# Main.net
KiCad netlist of a schematic drawn in Altium Designer
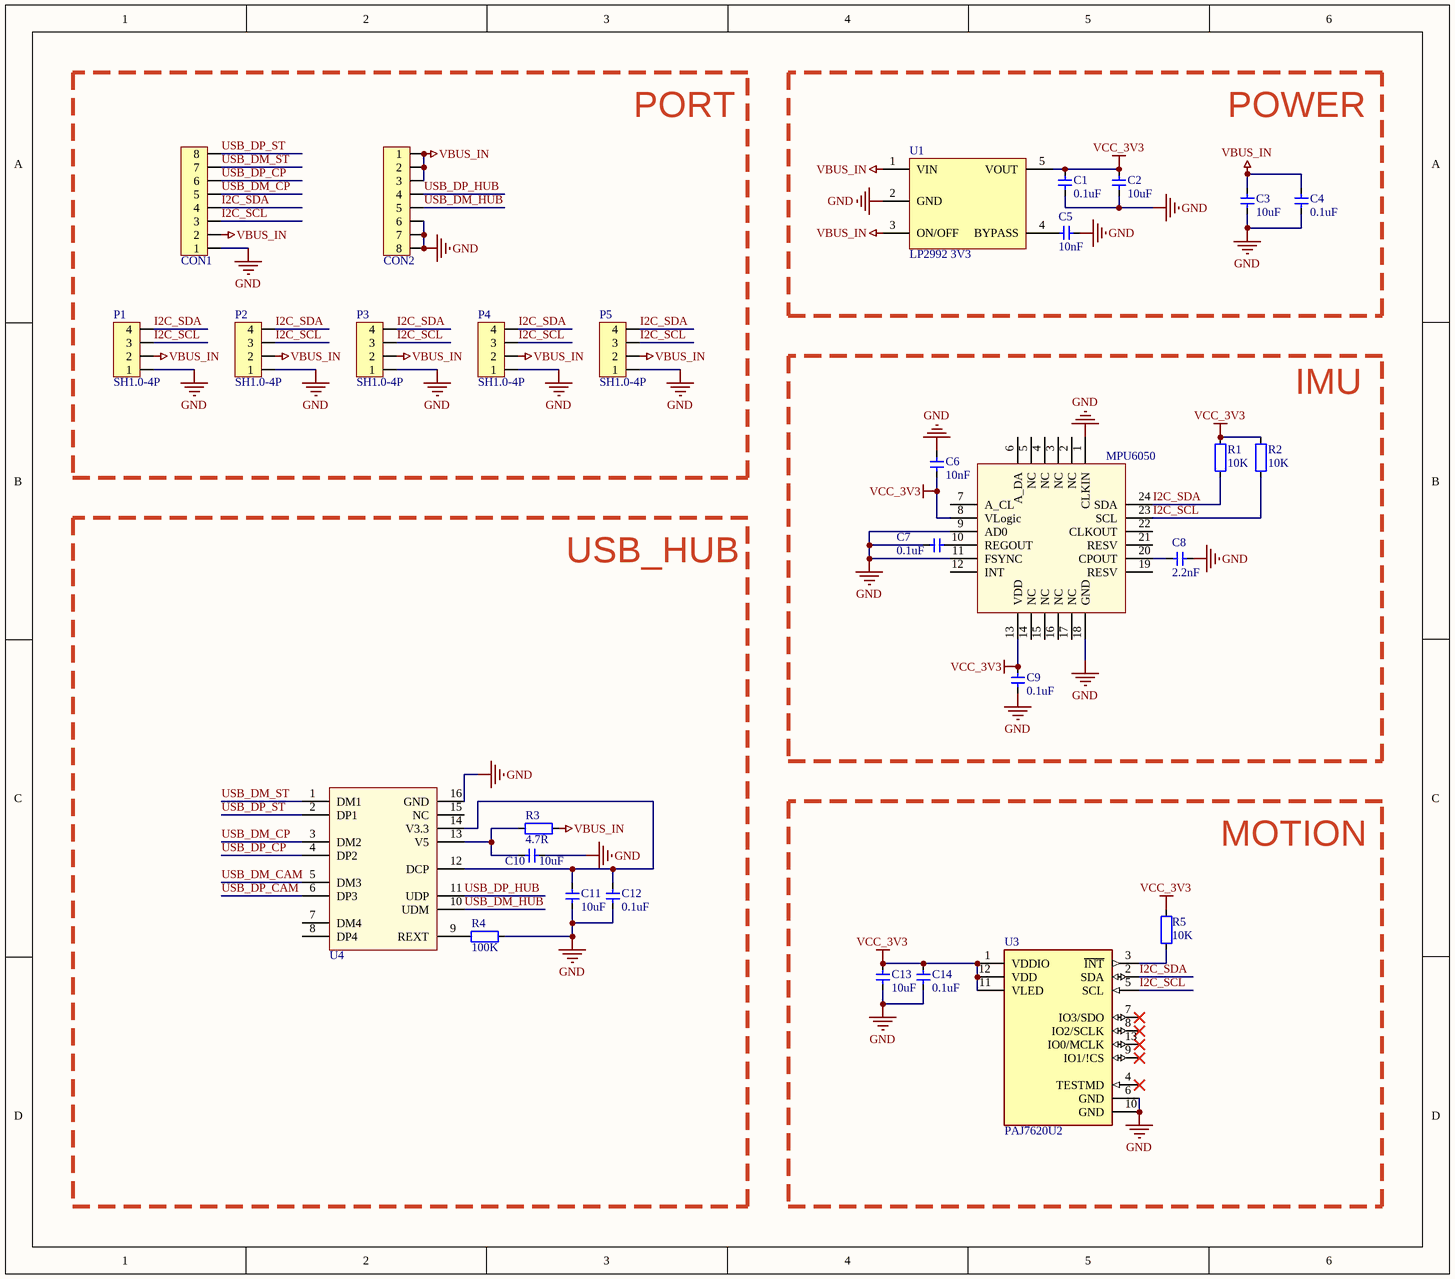
[diagram p0: Main.SchDoc]

(export (version "E")
  (design (tool "Eeschema 10.0.6"))
  (components
    (comp (ref "C1")
      (value "0.1uF")
      (footprint "CAP_0402")
      (description "Capacitor")
      (libsource (lib "MyPcbLib") (part "电容-0402"))
    )
    (comp (ref "C2")
      (value "10uF")
      (footprint "CAP_0402")
      (description "Capacitor")
      (libsource (lib "MyPcbLib") (part "电容-0402"))
    )
    (comp (ref "C3")
      (value "10uF")
      (footprint "CAP_0402")
      (description "Capacitor")
      (libsource (lib "MyPcbLib") (part "电容-0402"))
    )
    (comp (ref "C4")
      (value "0.1uF")
      (footprint "CAP_0402")
      (description "Capacitor")
      (libsource (lib "MyPcbLib") (part "电容-0402"))
    )
    (comp (ref "C5")
      (value "10nF")
      (footprint "CAP_0402")
      (description "Capacitor")
      (libsource (lib "MyPcbLib") (part "电容-0402"))
    )
    (comp (ref "C6")
      (value "10nF")
      (footprint "CAP_0402")
      (description "Capacitor")
      (libsource (lib "MyPcbLib") (part "电容-0402"))
    )
    (comp (ref "C7")
      (value "0.1uF")
      (footprint "CAP_0402")
      (description "Capacitor")
      (libsource (lib "MyPcbLib") (part "电容-0402"))
    )
    (comp (ref "C8")
      (value "2.2nF")
      (footprint "CAP_0402")
      (description "Capacitor")
      (libsource (lib "MyPcbLib") (part "电容-0402"))
    )
    (comp (ref "C9")
      (value "0.1uF")
      (footprint "CAP_0402")
      (description "Capacitor")
      (libsource (lib "MyPcbLib") (part "电容-0402"))
    )
    (comp (ref "C10")
      (value "10uF")
      (footprint "CAP_0402")
      (description "Capacitor")
      (libsource (lib "MyPcbLib") (part "电容-0402"))
    )
    (comp (ref "C11")
      (value "10uF")
      (footprint "CAP_0402")
      (description "Capacitor")
      (libsource (lib "MyPcbLib") (part "电容-0402"))
    )
    (comp (ref "C12")
      (value "0.1uF")
      (footprint "CAP_0402")
      (description "Capacitor")
      (libsource (lib "MyPcbLib") (part "电容-0402"))
    )
    (comp (ref "C13")
      (value "10uF")
      (footprint "CAP_0402")
      (description "Capacitor")
      (libsource (lib "MyPcbLib") (part "电容-0402"))
    )
    (comp (ref "C14")
      (value "0.1uF")
      (footprint "CAP_0402")
      (description "Capacitor")
      (libsource (lib "MyPcbLib") (part "电容-0402"))
    )
    (comp (ref "CON1")
      (value "FFC_0.5_8")
      (footprint "FFC_0.5_8")
      (description "FFC")
      (libsource (lib "KitSprout") (part "FFC_0.5_8"))
    )
    (comp (ref "CON2")
      (value "FFC_0.5_8")
      (footprint "FFC_0.5_8")
      (description "FFC")
      (libsource (lib "") (part "FFC_0.5_8_1"))
    )
    (comp (ref "P1") (value "SH1.0-4P") (footprint "SH1.0-4P") (libsource (lib "MyPcbLib") (part "SH1.0-4P")))
    (comp (ref "P2") (value "SH1.0-4P") (footprint "SH1.0-4P") (libsource (lib "MyPcbLib") (part "SH1.0-4P")))
    (comp (ref "P3") (value "SH1.0-4P") (footprint "SH1.0-4P") (libsource (lib "MyPcbLib") (part "SH1.0-4P")))
    (comp (ref "P4") (value "SH1.0-4P") (footprint "SH1.0-4P") (libsource (lib "MyPcbLib") (part "SH1.0-4P")))
    (comp (ref "P5") (value "SH1.0-4P") (footprint "SH1.0-4P") (libsource (lib "MyPcbLib") (part "SH1.0-4P")))
    (comp (ref "R1")
      (value "10K")
      (footprint "RES_0402")
      (description "Resistor")
      (libsource (lib "") (part "电阻-0402_1"))
    )
    (comp (ref "R2")
      (value "10K")
      (footprint "RES_0402")
      (description "Resistor")
      (libsource (lib "") (part "电阻-0402_1"))
    )
    (comp (ref "R3")
      (value "4.7R")
      (footprint "RES_0402")
      (description "Resistor")
      (libsource (lib "MyPcbLib") (part "电阻-0402"))
    )
    (comp (ref "R4")
      (value "100K")
      (footprint "RES_0402")
      (description "Resistor")
      (libsource (lib "MyPcbLib") (part "电阻-0402"))
    )
    (comp (ref "R5")
      (value "10K")
      (footprint "RES_0402")
      (description "Resistor")
      (libsource (lib "") (part "电阻-0402_2"))
    )
    (comp (ref "U1")
      (value "LP2992 3V3")
      (footprint "SOT23-5")
      (description "LDO")
      (libsource (lib "MyPcbLib") (part "LP2992"))
    )
    (comp (ref "U2")
      (value "MPU6050")
      (footprint "QFN-24")
      (description "六轴传感器")
      (libsource (lib "mLib") (part "MPU6050"))
    )
    (comp (ref "U3")
      (value "PAJ7620U2")
      (footprint "PAJ7620U2")
      (description "module sensorPAJ7620U2 : 54/TRAY, 5400/BOX, 32400/CARTON")
      (fields (field (name "MF") "Pixart"))
      (libsource (lib "MyPcbLib") (part "PAJ7620U2"))
    )
    (comp (ref "U4")
      (value "HS8836A")
      (footprint "SO-16N")
      (description "USB2.0 HUB")
      (libsource (lib "MyPcbLib") (part "HS8836A"))
    )
  )
  (nets
    (net (code "1") (name "/I2C_SCL") (class "Default")
      (node (ref "CON1") (pin "3") (pinfunction "3_3") (pintype "passive"))
      (node (ref "P1") (pin "3") (pinfunction "3_3") (pintype "passive"))
      (node (ref "P2") (pin "3") (pinfunction "3_3") (pintype "passive"))
      (node (ref "P3") (pin "3") (pinfunction "3_3") (pintype "passive"))
      (node (ref "P4") (pin "3") (pinfunction "3_3") (pintype "passive"))
      (node (ref "P5") (pin "3") (pinfunction "3_3") (pintype "passive"))
      (node (ref "R2") (pin "1") (pinfunction "1_1") (pintype "passive"))
      (node (ref "U2") (pin "23") (pinfunction "SCL_23") (pintype "passive"))
      (node (ref "U3") (pin "5") (pinfunction "SCL_5") (pintype "input"))
    )
    (net (code "2") (name "/I2C_SDA") (class "Default")
      (node (ref "CON1") (pin "4") (pinfunction "4_4") (pintype "passive"))
      (node (ref "P1") (pin "4") (pinfunction "4_4") (pintype "passive"))
      (node (ref "P2") (pin "4") (pinfunction "4_4") (pintype "passive"))
      (node (ref "P3") (pin "4") (pinfunction "4_4") (pintype "passive"))
      (node (ref "P4") (pin "4") (pinfunction "4_4") (pintype "passive"))
      (node (ref "P5") (pin "4") (pinfunction "4_4") (pintype "passive"))
      (node (ref "R1") (pin "1") (pinfunction "1_1") (pintype "passive"))
      (node (ref "U2") (pin "24") (pinfunction "SDA_24") (pintype "passive"))
      (node (ref "U3") (pin "2") (pinfunction "SDA_2") (pintype "bidirectional"))
    )
    (net (code "3") (name "/USB_DM_CAM") (class "Default")
      (node (ref "U4") (pin "5") (pinfunction "DM3_5") (pintype "passive"))
    )
    (net (code "4") (name "/USB_DM_CP") (class "Default")
      (node (ref "CON1") (pin "5") (pinfunction "5_5") (pintype "passive"))
      (node (ref "U4") (pin "3") (pinfunction "DM2_3") (pintype "passive"))
    )
    (net (code "5") (name "/USB_DM_HUB") (class "Default")
      (node (ref "CON2") (pin "5") (pinfunction "5_5") (pintype "passive"))
      (node (ref "U4") (pin "10") (pinfunction "UDM_10") (pintype "passive"))
    )
    (net (code "6") (name "/USB_DM_ST") (class "Default")
      (node (ref "CON1") (pin "7") (pinfunction "7_7") (pintype "passive"))
      (node (ref "U4") (pin "1") (pinfunction "DM1_1") (pintype "passive"))
    )
    (net (code "7") (name "/USB_DP_CAM") (class "Default")
      (node (ref "U4") (pin "6") (pinfunction "DP3_6") (pintype "passive"))
    )
    (net (code "8") (name "/USB_DP_CP") (class "Default")
      (node (ref "CON1") (pin "6") (pinfunction "6_6") (pintype "passive"))
      (node (ref "U4") (pin "4") (pinfunction "DP2_4") (pintype "passive"))
    )
    (net (code "9") (name "/USB_DP_HUB") (class "Default")
      (node (ref "CON2") (pin "4") (pinfunction "4_4") (pintype "passive"))
      (node (ref "U4") (pin "11") (pinfunction "UDP_11") (pintype "passive"))
    )
    (net (code "10") (name "/USB_DP_ST") (class "Default")
      (node (ref "CON1") (pin "8") (pinfunction "8_8") (pintype "passive"))
      (node (ref "U4") (pin "2") (pinfunction "DP1_2") (pintype "passive"))
    )
    (net (code "11") (name "GND") (class "Default")
      (node (ref "C1") (pin "1") (pinfunction "1_1") (pintype "passive"))
      (node (ref "C10") (pin "1") (pinfunction "1_1") (pintype "passive"))
      (node (ref "C11") (pin "2") (pinfunction "2_2") (pintype "passive"))
      (node (ref "C12") (pin "2") (pinfunction "2_2") (pintype "passive"))
      (node (ref "C13") (pin "2") (pinfunction "2_2") (pintype "passive"))
      (node (ref "C14") (pin "2") (pinfunction "2_2") (pintype "passive"))
      (node (ref "C2") (pin "1") (pinfunction "1_1") (pintype "passive"))
      (node (ref "C3") (pin "1") (pinfunction "1_1") (pintype "passive"))
      (node (ref "C4") (pin "1") (pinfunction "1_1") (pintype "passive"))
      (node (ref "C5") (pin "1") (pinfunction "1_1") (pintype "passive"))
      (node (ref "C6") (pin "2") (pinfunction "2_2") (pintype "passive"))
      (node (ref "C7") (pin "2") (pinfunction "2_2") (pintype "passive"))
      (node (ref "C8") (pin "1") (pinfunction "1_1") (pintype "passive"))
      (node (ref "C9") (pin "1") (pinfunction "1_1") (pintype "passive"))
      (node (ref "CON1") (pin "1") (pinfunction "1_1") (pintype "passive"))
      (node (ref "CON2") (pin "6") (pinfunction "6_6") (pintype "passive"))
      (node (ref "CON2") (pin "7") (pinfunction "7_7") (pintype "passive"))
      (node (ref "CON2") (pin "8") (pinfunction "8_8") (pintype "passive"))
      (node (ref "P1") (pin "1") (pinfunction "1_1") (pintype "passive"))
      (node (ref "P2") (pin "1") (pinfunction "1_1") (pintype "passive"))
      (node (ref "P3") (pin "1") (pinfunction "1_1") (pintype "passive"))
      (node (ref "P4") (pin "1") (pinfunction "1_1") (pintype "passive"))
      (node (ref "P5") (pin "1") (pinfunction "1_1") (pintype "passive"))
      (node (ref "R4") (pin "1") (pinfunction "1_1") (pintype "passive"))
      (node (ref "U1") (pin "2") (pinfunction "GND_2") (pintype "passive"))
      (node (ref "U2") (pin "1") (pinfunction "CLKIN_1") (pintype "passive"))
      (node (ref "U2") (pin "11") (pinfunction "FSYNC_11") (pintype "passive"))
      (node (ref "U2") (pin "18") (pinfunction "GND_18") (pintype "passive"))
      (node (ref "U2") (pin "9") (pinfunction "AD0_9") (pintype "passive"))
      (node (ref "U3") (pin "10") (pinfunction "GND_10") (pintype "passive"))
      (node (ref "U3") (pin "6") (pinfunction "GND_6") (pintype "passive"))
      (node (ref "U4") (pin "16") (pinfunction "GND_16") (pintype "passive"))
    )
    (net (code "12") (name "Net-(U1-BYPASS)") (class "Default")
      (node (ref "C5") (pin "2") (pinfunction "2_2") (pintype "passive"))
      (node (ref "U1") (pin "4") (pinfunction "BYPASS_4") (pintype "passive"))
    )
    (net (code "13") (name "Net-(U2-CPOUT)") (class "Default")
      (node (ref "C8") (pin "2") (pinfunction "2_2") (pintype "passive"))
      (node (ref "U2") (pin "20") (pinfunction "CPOUT_20") (pintype "passive"))
    )
    (net (code "14") (name "Net-(U2-REGOUT)") (class "Default")
      (node (ref "C7") (pin "1") (pinfunction "1_1") (pintype "passive"))
      (node (ref "U2") (pin "10") (pinfunction "REGOUT_10") (pintype "passive"))
    )
    (net (code "15") (name "Net-(U3-~{INT})") (class "Default")
      (node (ref "R5") (pin "2") (pinfunction "2_2") (pintype "passive"))
      (node (ref "U3") (pin "3") (pinfunction "~{INT}_3") (pintype "output"))
    )
    (net (code "16") (name "Net-(U4-DCP)") (class "Default")
      (node (ref "C11") (pin "1") (pinfunction "1_1") (pintype "passive"))
      (node (ref "C12") (pin "1") (pinfunction "1_1") (pintype "passive"))
      (node (ref "U4") (pin "12") (pinfunction "DCP_12") (pintype "passive"))
      (node (ref "U4") (pin "14") (pinfunction "V3.3_14") (pintype "passive"))
    )
    (net (code "17") (name "Net-(U4-REXT)") (class "Default")
      (node (ref "R4") (pin "2") (pinfunction "2_2") (pintype "passive"))
      (node (ref "U4") (pin "9") (pinfunction "REXT_9") (pintype "passive"))
    )
    (net (code "18") (name "Net-(U4-V5)") (class "Default")
      (node (ref "C10") (pin "2") (pinfunction "2_2") (pintype "passive"))
      (node (ref "R3") (pin "2") (pinfunction "2_2") (pintype "passive"))
      (node (ref "U4") (pin "13") (pinfunction "V5_13") (pintype "passive"))
    )
    (net (code "19") (name "VBUS_IN") (class "Default")
      (node (ref "C3") (pin "2") (pinfunction "2_2") (pintype "passive"))
      (node (ref "C4") (pin "2") (pinfunction "2_2") (pintype "passive"))
      (node (ref "CON1") (pin "2") (pinfunction "2_2") (pintype "passive"))
      (node (ref "CON2") (pin "1") (pinfunction "1_1") (pintype "passive"))
      (node (ref "CON2") (pin "2") (pinfunction "2_2") (pintype "passive"))
      (node (ref "CON2") (pin "3") (pinfunction "3_3") (pintype "passive"))
      (node (ref "P1") (pin "2") (pinfunction "2_2") (pintype "passive"))
      (node (ref "P2") (pin "2") (pinfunction "2_2") (pintype "passive"))
      (node (ref "P3") (pin "2") (pinfunction "2_2") (pintype "passive"))
      (node (ref "P4") (pin "2") (pinfunction "2_2") (pintype "passive"))
      (node (ref "P5") (pin "2") (pinfunction "2_2") (pintype "passive"))
      (node (ref "R3") (pin "1") (pinfunction "1_1") (pintype "passive"))
      (node (ref "U1") (pin "1") (pinfunction "VIN_1") (pintype "passive"))
      (node (ref "U1") (pin "3") (pinfunction "ON/OFF_3") (pintype "passive"))
    )
    (net (code "20") (name "VCC_3V3") (class "Default")
      (node (ref "C1") (pin "2") (pinfunction "2_2") (pintype "passive"))
      (node (ref "C13") (pin "1") (pinfunction "1_1") (pintype "passive"))
      (node (ref "C14") (pin "1") (pinfunction "1_1") (pintype "passive"))
      (node (ref "C2") (pin "2") (pinfunction "2_2") (pintype "passive"))
      (node (ref "C6") (pin "1") (pinfunction "1_1") (pintype "passive"))
      (node (ref "C9") (pin "2") (pinfunction "2_2") (pintype "passive"))
      (node (ref "R1") (pin "2") (pinfunction "2_2") (pintype "passive"))
      (node (ref "R2") (pin "2") (pinfunction "2_2") (pintype "passive"))
      (node (ref "R5") (pin "1") (pinfunction "1_1") (pintype "passive"))
      (node (ref "U1") (pin "5") (pinfunction "VOUT_5") (pintype "passive"))
      (node (ref "U2") (pin "13") (pinfunction "VDD_13") (pintype "passive"))
      (node (ref "U2") (pin "8") (pinfunction "VLogic_8") (pintype "passive"))
      (node (ref "U3") (pin "1") (pinfunction "VDDIO_1") (pintype "power_in"))
      (node (ref "U3") (pin "11") (pinfunction "VLED_11") (pintype "power_in"))
      (node (ref "U3") (pin "12") (pinfunction "VDD_12") (pintype "power_in"))
    )
    (net (code "21") (name "unconnected-(U2-A_CL-Pad7)") (class "Default")
      (node (ref "U2") (pin "7") (pinfunction "A_CL_7") (pintype "passive"))
    )
    (net (code "22") (name "unconnected-(U2-A_DA-Pad6)") (class "Default")
      (node (ref "U2") (pin "6") (pinfunction "A_DA_6") (pintype "passive"))
    )
    (net (code "23") (name "unconnected-(U2-CLKOUT-Pad22)") (class "Default")
      (node (ref "U2") (pin "22") (pinfunction "CLKOUT_22") (pintype "passive"))
    )
    (net (code "24") (name "unconnected-(U2-INT-Pad12)") (class "Default")
      (node (ref "U2") (pin "12") (pinfunction "INT_12") (pintype "passive"))
    )
    (net (code "25") (name "unconnected-(U2-NC-Pad2)") (class "Default")
      (node (ref "U2") (pin "2") (pinfunction "NC_2") (pintype "passive"))
    )
    (net (code "26") (name "unconnected-(U2-NC-Pad3)") (class "Default")
      (node (ref "U2") (pin "3") (pinfunction "NC_3") (pintype "passive"))
    )
    (net (code "27") (name "unconnected-(U2-NC-Pad4)") (class "Default")
      (node (ref "U2") (pin "4") (pinfunction "NC_4") (pintype "passive"))
    )
    (net (code "28") (name "unconnected-(U2-NC-Pad5)") (class "Default")
      (node (ref "U2") (pin "5") (pinfunction "NC_5") (pintype "passive"))
    )
    (net (code "29") (name "unconnected-(U2-NC-Pad14)") (class "Default")
      (node (ref "U2") (pin "14") (pinfunction "NC_14") (pintype "passive"))
    )
    (net (code "30") (name "unconnected-(U2-NC-Pad15)") (class "Default")
      (node (ref "U2") (pin "15") (pinfunction "NC_15") (pintype "passive"))
    )
    (net (code "31") (name "unconnected-(U2-NC-Pad16)") (class "Default")
      (node (ref "U2") (pin "16") (pinfunction "NC_16") (pintype "passive"))
    )
    (net (code "32") (name "unconnected-(U2-NC-Pad17)") (class "Default")
      (node (ref "U2") (pin "17") (pinfunction "NC_17") (pintype "passive"))
    )
    (net (code "33") (name "unconnected-(U2-RESV-Pad19)") (class "Default")
      (node (ref "U2") (pin "19") (pinfunction "RESV_19") (pintype "passive"))
    )
    (net (code "34") (name "unconnected-(U2-RESV-Pad21)") (class "Default")
      (node (ref "U2") (pin "21") (pinfunction "RESV_21") (pintype "passive"))
    )
    (net (code "35") (name "unconnected-(U3-IO0{slash}MCLK-Pad13)") (class "Default")
      (node (ref "U3") (pin "13") (pinfunction "IO0/MCLK_13") (pintype "bidirectional+no_connect"))
    )
    (net (code "36") (name "unconnected-(U3-IO1{slash}!CS-Pad9)") (class "Default")
      (node (ref "U3") (pin "9") (pinfunction "IO1/!CS_9") (pintype "bidirectional+no_connect"))
    )
    (net (code "37") (name "unconnected-(U3-IO2{slash}SCLK-Pad8)") (class "Default")
      (node (ref "U3") (pin "8") (pinfunction "IO2/SCLK_8") (pintype "bidirectional+no_connect"))
    )
    (net (code "38") (name "unconnected-(U3-IO3{slash}SDO-Pad7)") (class "Default")
      (node (ref "U3") (pin "7") (pinfunction "IO3/SDO_7") (pintype "bidirectional+no_connect"))
    )
    (net (code "39") (name "unconnected-(U3-TESTMD-Pad4)") (class "Default")
      (node (ref "U3") (pin "4") (pinfunction "TESTMD_4") (pintype "input+no_connect"))
    )
    (net (code "40") (name "unconnected-(U4-DM4-Pad7)") (class "Default")
      (node (ref "U4") (pin "7") (pinfunction "DM4_7") (pintype "passive"))
    )
    (net (code "41") (name "unconnected-(U4-DP4-Pad8)") (class "Default")
      (node (ref "U4") (pin "8") (pinfunction "DP4_8") (pintype "passive"))
    )
    (net (code "42") (name "unconnected-(U4-NC-Pad15)") (class "Default")
      (node (ref "U4") (pin "15") (pinfunction "NC_15") (pintype "passive"))
    )
  )
)
